# conectic_to_girouette.net
KiCad netlist of a schematic drawn in Altium Designer
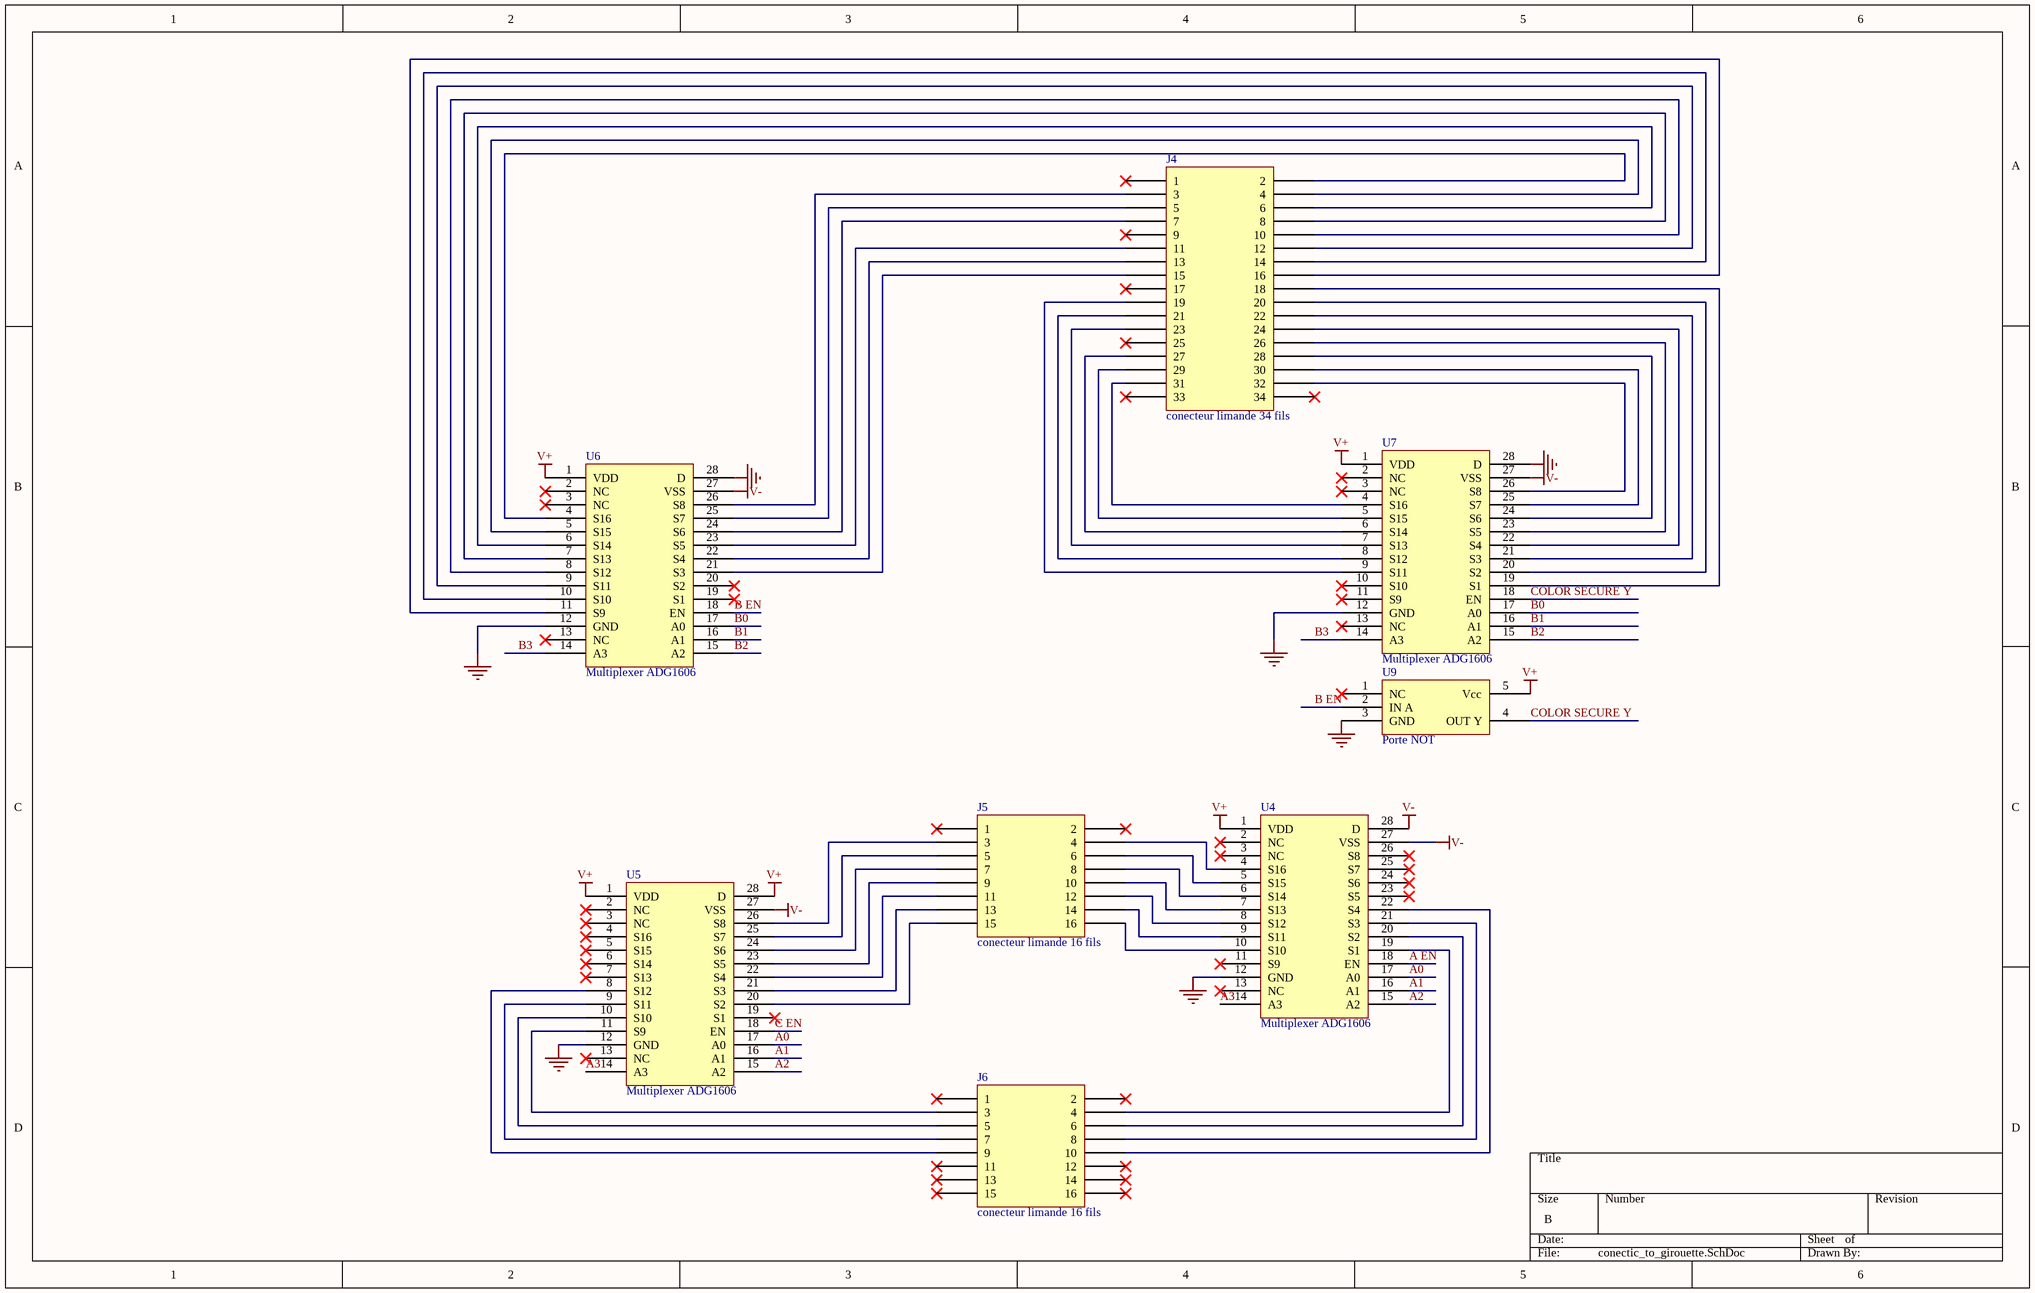
[diagram p0: conectic_to_girouette.SchDoc]

(export (version "E")
  (design (tool "Eeschema 10.0.6"))
  (components
    (comp (ref "J4")
      (value "conecteur limande 34 fils")
      (footprint "HTSS-117-01-T-DV-P-TR Connecteur 34 pins")
      (libsource (lib "lib_protoboard") (part "Limande 34 fils"))
    )
    (comp (ref "J5")
      (value "conecteur limande 16 fils")
      (footprint "M80-8541642 connecteur 16 pins")
      (libsource (lib "lib_protoboard") (part "Connecteur carte a carte"))
    )
    (comp (ref "J6")
      (value "conecteur limande 16 fils")
      (footprint "M80-8541642 connecteur 16 pins")
      (libsource (lib "lib_protoboard") (part "Connecteur carte a carte"))
    )
    (comp (ref "U4")
      (value "Multiplexer ADG1606")
      (footprint "TSOP65P640X120-28N")
      (libsource (lib "ADG1606") (part "Component_1"))
    )
    (comp (ref "U5")
      (value "Multiplexer ADG1606")
      (footprint "TSOP65P640X120-28N")
      (libsource (lib "ADG1606") (part "Component_1"))
    )
    (comp (ref "U6")
      (value "Multiplexer ADG1606")
      (footprint "TSOP65P640X120-28N")
      (libsource (lib "lib_protoboard") (part "ADG1606"))
    )
    (comp (ref "U7")
      (value "Multiplexer ADG1606")
      (footprint "TSOP65P640X120-28N")
      (libsource (lib "lib_protoboard") (part "ADG1606"))
    )
    (comp (ref "U9")
      (value "Porte NOT")
      (footprint "SOT65P210X110-5N")
      (libsource (lib "lib_protoboard") (part "Porte NOT"))
    )
  )
  (nets
    (net (code "1") (name "/A EN") (class "Default")
      (node (ref "U4") (pin "18") (pinfunction "EN_18") (pintype "passive"))
    )
    (net (code "2") (name "/A0") (class "Default")
      (node (ref "U4") (pin "17") (pinfunction "A0_17") (pintype "passive"))
      (node (ref "U5") (pin "17") (pinfunction "A0_17") (pintype "passive"))
    )
    (net (code "3") (name "/A1") (class "Default")
      (node (ref "U4") (pin "16") (pinfunction "A1_16") (pintype "passive"))
      (node (ref "U5") (pin "16") (pinfunction "A1_16") (pintype "passive"))
    )
    (net (code "4") (name "/A2") (class "Default")
      (node (ref "U4") (pin "15") (pinfunction "A2_15") (pintype "passive"))
      (node (ref "U5") (pin "15") (pinfunction "A2_15") (pintype "passive"))
    )
    (net (code "5") (name "/A3") (class "Default")
      (node (ref "U4") (pin "14") (pinfunction "A3_14") (pintype "passive"))
      (node (ref "U5") (pin "14") (pinfunction "A3_14") (pintype "passive"))
    )
    (net (code "6") (name "/B EN") (class "Default")
      (node (ref "U6") (pin "18") (pinfunction "EN_18") (pintype "passive"))
      (node (ref "U9") (pin "2") (pinfunction "IN_A_2") (pintype "passive"))
    )
    (net (code "7") (name "/B0") (class "Default")
      (node (ref "U6") (pin "17") (pinfunction "A0_17") (pintype "passive"))
      (node (ref "U7") (pin "17") (pinfunction "A0_17") (pintype "passive"))
    )
    (net (code "8") (name "/B1") (class "Default")
      (node (ref "U6") (pin "16") (pinfunction "A1_16") (pintype "passive"))
      (node (ref "U7") (pin "16") (pinfunction "A1_16") (pintype "passive"))
    )
    (net (code "9") (name "/B2") (class "Default")
      (node (ref "U6") (pin "15") (pinfunction "A2_15") (pintype "passive"))
      (node (ref "U7") (pin "15") (pinfunction "A2_15") (pintype "passive"))
    )
    (net (code "10") (name "/B3") (class "Default")
      (node (ref "U6") (pin "14") (pinfunction "A3_14") (pintype "passive"))
      (node (ref "U7") (pin "14") (pinfunction "A3_14") (pintype "passive"))
    )
    (net (code "11") (name "/C EN") (class "Default")
      (node (ref "U5") (pin "18") (pinfunction "EN_18") (pintype "passive"))
    )
    (net (code "12") (name "/COLOR SECURE Y") (class "Default")
      (node (ref "U7") (pin "18") (pinfunction "EN_18") (pintype "passive"))
      (node (ref "U9") (pin "4") (pinfunction "OUT_Y_4") (pintype "passive"))
    )
    (net (code "13") (name "GND") (class "Default")
      (node (ref "U4") (pin "12") (pinfunction "GND_12") (pintype "passive"))
      (node (ref "U5") (pin "12") (pinfunction "GND_12") (pintype "passive"))
      (node (ref "U6") (pin "12") (pinfunction "GND_12") (pintype "passive"))
      (node (ref "U6") (pin "28") (pinfunction "D_28") (pintype "passive"))
      (node (ref "U7") (pin "12") (pinfunction "GND_12") (pintype "passive"))
      (node (ref "U7") (pin "28") (pinfunction "D_28") (pintype "passive"))
      (node (ref "U9") (pin "3") (pinfunction "GND_3") (pintype "passive"))
    )
    (net (code "14") (name "Net-(U4-S1)") (class "Default")
      (node (ref "J6") (pin "4") (pinfunction "4_4") (pintype "passive"))
      (node (ref "U4") (pin "19") (pinfunction "S1_19") (pintype "passive"))
    )
    (net (code "15") (name "Net-(U4-S2)") (class "Default")
      (node (ref "J6") (pin "6") (pinfunction "6_6") (pintype "passive"))
      (node (ref "U4") (pin "20") (pinfunction "S2_20") (pintype "passive"))
    )
    (net (code "16") (name "Net-(U4-S3)") (class "Default")
      (node (ref "J6") (pin "8") (pinfunction "8_8") (pintype "passive"))
      (node (ref "U4") (pin "21") (pinfunction "S3_21") (pintype "passive"))
    )
    (net (code "17") (name "Net-(U4-S4)") (class "Default")
      (node (ref "J6") (pin "10") (pinfunction "10_10") (pintype "passive"))
      (node (ref "U4") (pin "22") (pinfunction "S4_22") (pintype "passive"))
    )
    (net (code "18") (name "Net-(U4-S10)") (class "Default")
      (node (ref "J5") (pin "16") (pinfunction "16_16") (pintype "passive"))
      (node (ref "U4") (pin "10") (pinfunction "S10_10") (pintype "passive"))
    )
    (net (code "19") (name "Net-(U4-S11)") (class "Default")
      (node (ref "J5") (pin "14") (pinfunction "14_14") (pintype "passive"))
      (node (ref "U4") (pin "9") (pinfunction "S11_9") (pintype "passive"))
    )
    (net (code "20") (name "Net-(U4-S12)") (class "Default")
      (node (ref "J5") (pin "12") (pinfunction "12_12") (pintype "passive"))
      (node (ref "U4") (pin "8") (pinfunction "S12_8") (pintype "passive"))
    )
    (net (code "21") (name "Net-(U4-S13)") (class "Default")
      (node (ref "J5") (pin "10") (pinfunction "10_10") (pintype "passive"))
      (node (ref "U4") (pin "7") (pinfunction "S13_7") (pintype "passive"))
    )
    (net (code "22") (name "Net-(U4-S14)") (class "Default")
      (node (ref "J5") (pin "8") (pinfunction "8_8") (pintype "passive"))
      (node (ref "U4") (pin "6") (pinfunction "S14_6") (pintype "passive"))
    )
    (net (code "23") (name "Net-(U4-S15)") (class "Default")
      (node (ref "J5") (pin "6") (pinfunction "6_6") (pintype "passive"))
      (node (ref "U4") (pin "5") (pinfunction "S15_5") (pintype "passive"))
    )
    (net (code "24") (name "Net-(U4-S16)") (class "Default")
      (node (ref "J5") (pin "4") (pinfunction "4_4") (pintype "passive"))
      (node (ref "U4") (pin "4") (pinfunction "S16_4") (pintype "passive"))
    )
    (net (code "25") (name "Net-(U5-S2)") (class "Default")
      (node (ref "J5") (pin "15") (pinfunction "15_15") (pintype "passive"))
      (node (ref "U5") (pin "20") (pinfunction "S2_20") (pintype "passive"))
    )
    (net (code "26") (name "Net-(U5-S3)") (class "Default")
      (node (ref "J5") (pin "13") (pinfunction "13_13") (pintype "passive"))
      (node (ref "U5") (pin "21") (pinfunction "S3_21") (pintype "passive"))
    )
    (net (code "27") (name "Net-(U5-S4)") (class "Default")
      (node (ref "J5") (pin "11") (pinfunction "11_11") (pintype "passive"))
      (node (ref "U5") (pin "22") (pinfunction "S4_22") (pintype "passive"))
    )
    (net (code "28") (name "Net-(U5-S5)") (class "Default")
      (node (ref "J5") (pin "9") (pinfunction "9_9") (pintype "passive"))
      (node (ref "U5") (pin "23") (pinfunction "S5_23") (pintype "passive"))
    )
    (net (code "29") (name "Net-(U5-S6)") (class "Default")
      (node (ref "J5") (pin "7") (pinfunction "7_7") (pintype "passive"))
      (node (ref "U5") (pin "24") (pinfunction "S6_24") (pintype "passive"))
    )
    (net (code "30") (name "Net-(U5-S7)") (class "Default")
      (node (ref "J5") (pin "5") (pinfunction "5_5") (pintype "passive"))
      (node (ref "U5") (pin "25") (pinfunction "S7_25") (pintype "passive"))
    )
    (net (code "31") (name "Net-(U5-S8)") (class "Default")
      (node (ref "J5") (pin "3") (pinfunction "3_3") (pintype "passive"))
      (node (ref "U5") (pin "26") (pinfunction "S8_26") (pintype "passive"))
    )
    (net (code "32") (name "Net-(U5-S9)") (class "Default")
      (node (ref "J6") (pin "3") (pinfunction "3_3") (pintype "passive"))
      (node (ref "U5") (pin "11") (pinfunction "S9_11") (pintype "passive"))
    )
    (net (code "33") (name "Net-(U5-S10)") (class "Default")
      (node (ref "J6") (pin "5") (pinfunction "5_5") (pintype "passive"))
      (node (ref "U5") (pin "10") (pinfunction "S10_10") (pintype "passive"))
    )
    (net (code "34") (name "Net-(U5-S11)") (class "Default")
      (node (ref "J6") (pin "7") (pinfunction "7_7") (pintype "passive"))
      (node (ref "U5") (pin "9") (pinfunction "S11_9") (pintype "passive"))
    )
    (net (code "35") (name "Net-(U5-S12)") (class "Default")
      (node (ref "J6") (pin "9") (pinfunction "9_9") (pintype "passive"))
      (node (ref "U5") (pin "8") (pinfunction "S12_8") (pintype "passive"))
    )
    (net (code "36") (name "Net-(U6-S3)") (class "Default")
      (node (ref "J4") (pin "15") (pinfunction "15_15") (pintype "passive"))
      (node (ref "U6") (pin "21") (pinfunction "S3_21") (pintype "passive"))
    )
    (net (code "37") (name "Net-(U6-S4)") (class "Default")
      (node (ref "J4") (pin "13") (pinfunction "13_13") (pintype "passive"))
      (node (ref "U6") (pin "22") (pinfunction "S4_22") (pintype "passive"))
    )
    (net (code "38") (name "Net-(U6-S5)") (class "Default")
      (node (ref "J4") (pin "11") (pinfunction "11_11") (pintype "passive"))
      (node (ref "U6") (pin "23") (pinfunction "S5_23") (pintype "passive"))
    )
    (net (code "39") (name "Net-(U6-S6)") (class "Default")
      (node (ref "J4") (pin "7") (pinfunction "7_7") (pintype "passive"))
      (node (ref "U6") (pin "24") (pinfunction "S6_24") (pintype "passive"))
    )
    (net (code "40") (name "Net-(U6-S7)") (class "Default")
      (node (ref "J4") (pin "5") (pinfunction "5_5") (pintype "passive"))
      (node (ref "U6") (pin "25") (pinfunction "S7_25") (pintype "passive"))
    )
    (net (code "41") (name "Net-(U6-S8)") (class "Default")
      (node (ref "J4") (pin "3") (pinfunction "3_3") (pintype "passive"))
      (node (ref "U6") (pin "26") (pinfunction "S8_26") (pintype "passive"))
    )
    (net (code "42") (name "Net-(U6-S9)") (class "Default")
      (node (ref "J4") (pin "16") (pinfunction "16_16") (pintype "passive"))
      (node (ref "U6") (pin "11") (pinfunction "S9_11") (pintype "passive"))
    )
    (net (code "43") (name "Net-(U6-S10)") (class "Default")
      (node (ref "J4") (pin "14") (pinfunction "14_14") (pintype "passive"))
      (node (ref "U6") (pin "10") (pinfunction "S10_10") (pintype "passive"))
    )
    (net (code "44") (name "Net-(U6-S11)") (class "Default")
      (node (ref "J4") (pin "12") (pinfunction "12_12") (pintype "passive"))
      (node (ref "U6") (pin "9") (pinfunction "S11_9") (pintype "passive"))
    )
    (net (code "45") (name "Net-(U6-S12)") (class "Default")
      (node (ref "J4") (pin "10") (pinfunction "10_10") (pintype "passive"))
      (node (ref "U6") (pin "8") (pinfunction "S12_8") (pintype "passive"))
    )
    (net (code "46") (name "Net-(U6-S13)") (class "Default")
      (node (ref "J4") (pin "8") (pinfunction "8_8") (pintype "passive"))
      (node (ref "U6") (pin "7") (pinfunction "S13_7") (pintype "passive"))
    )
    (net (code "47") (name "Net-(U6-S14)") (class "Default")
      (node (ref "J4") (pin "6") (pinfunction "6_6") (pintype "passive"))
      (node (ref "U6") (pin "6") (pinfunction "S14_6") (pintype "passive"))
    )
    (net (code "48") (name "Net-(U6-S15)") (class "Default")
      (node (ref "J4") (pin "4") (pinfunction "4_4") (pintype "passive"))
      (node (ref "U6") (pin "5") (pinfunction "S15_5") (pintype "passive"))
    )
    (net (code "49") (name "Net-(U6-S16)") (class "Default")
      (node (ref "J4") (pin "2") (pinfunction "2_2") (pintype "passive"))
      (node (ref "U6") (pin "4") (pinfunction "S16_4") (pintype "passive"))
    )
    (net (code "50") (name "Net-(U7-S1)") (class "Default")
      (node (ref "J4") (pin "18") (pinfunction "18_18") (pintype "passive"))
      (node (ref "U7") (pin "19") (pinfunction "S1_19") (pintype "passive"))
    )
    (net (code "51") (name "Net-(U7-S2)") (class "Default")
      (node (ref "J4") (pin "20") (pinfunction "20_20") (pintype "passive"))
      (node (ref "U7") (pin "20") (pinfunction "S2_20") (pintype "passive"))
    )
    (net (code "52") (name "Net-(U7-S3)") (class "Default")
      (node (ref "J4") (pin "22") (pinfunction "22_22") (pintype "passive"))
      (node (ref "U7") (pin "21") (pinfunction "S3_21") (pintype "passive"))
    )
    (net (code "53") (name "Net-(U7-S4)") (class "Default")
      (node (ref "J4") (pin "24") (pinfunction "24_24") (pintype "passive"))
      (node (ref "U7") (pin "22") (pinfunction "S4_22") (pintype "passive"))
    )
    (net (code "54") (name "Net-(U7-S5)") (class "Default")
      (node (ref "J4") (pin "26") (pinfunction "26_26") (pintype "passive"))
      (node (ref "U7") (pin "23") (pinfunction "S5_23") (pintype "passive"))
    )
    (net (code "55") (name "Net-(U7-S6)") (class "Default")
      (node (ref "J4") (pin "28") (pinfunction "28_28") (pintype "passive"))
      (node (ref "U7") (pin "24") (pinfunction "S6_24") (pintype "passive"))
    )
    (net (code "56") (name "Net-(U7-S7)") (class "Default")
      (node (ref "J4") (pin "30") (pinfunction "30_30") (pintype "passive"))
      (node (ref "U7") (pin "25") (pinfunction "S7_25") (pintype "passive"))
    )
    (net (code "57") (name "Net-(U7-S8)") (class "Default")
      (node (ref "J4") (pin "32") (pinfunction "32_32") (pintype "passive"))
      (node (ref "U7") (pin "26") (pinfunction "S8_26") (pintype "passive"))
    )
    (net (code "58") (name "Net-(U7-S11)") (class "Default")
      (node (ref "J4") (pin "19") (pinfunction "19_19") (pintype "passive"))
      (node (ref "U7") (pin "9") (pinfunction "S11_9") (pintype "passive"))
    )
    (net (code "59") (name "Net-(U7-S12)") (class "Default")
      (node (ref "J4") (pin "21") (pinfunction "21_21") (pintype "passive"))
      (node (ref "U7") (pin "8") (pinfunction "S12_8") (pintype "passive"))
    )
    (net (code "60") (name "Net-(U7-S13)") (class "Default")
      (node (ref "J4") (pin "23") (pinfunction "23_23") (pintype "passive"))
      (node (ref "U7") (pin "7") (pinfunction "S13_7") (pintype "passive"))
    )
    (net (code "61") (name "Net-(U7-S14)") (class "Default")
      (node (ref "J4") (pin "27") (pinfunction "27_27") (pintype "passive"))
      (node (ref "U7") (pin "6") (pinfunction "S14_6") (pintype "passive"))
    )
    (net (code "62") (name "Net-(U7-S15)") (class "Default")
      (node (ref "J4") (pin "29") (pinfunction "29_29") (pintype "passive"))
      (node (ref "U7") (pin "5") (pinfunction "S15_5") (pintype "passive"))
    )
    (net (code "63") (name "Net-(U7-S16)") (class "Default")
      (node (ref "J4") (pin "31") (pinfunction "31_31") (pintype "passive"))
      (node (ref "U7") (pin "4") (pinfunction "S16_4") (pintype "passive"))
    )
    (net (code "64") (name "V+") (class "Default")
      (node (ref "U4") (pin "1") (pinfunction "VDD_1") (pintype "passive"))
      (node (ref "U5") (pin "1") (pinfunction "VDD_1") (pintype "passive"))
      (node (ref "U5") (pin "28") (pinfunction "D_28") (pintype "passive"))
      (node (ref "U6") (pin "1") (pinfunction "VDD_1") (pintype "passive"))
      (node (ref "U7") (pin "1") (pinfunction "VDD_1") (pintype "passive"))
      (node (ref "U9") (pin "5") (pinfunction "Vcc_5") (pintype "passive"))
    )
    (net (code "65") (name "V-") (class "Default")
      (node (ref "U4") (pin "27") (pinfunction "VSS_27") (pintype "passive"))
      (node (ref "U4") (pin "28") (pinfunction "D_28") (pintype "passive"))
      (node (ref "U5") (pin "27") (pinfunction "VSS_27") (pintype "passive"))
      (node (ref "U6") (pin "27") (pinfunction "VSS_27") (pintype "passive"))
      (node (ref "U7") (pin "27") (pinfunction "VSS_27") (pintype "passive"))
    )
    (net (code "66") (name "unconnected-(J4-Pad1)") (class "Default")
      (node (ref "J4") (pin "1") (pinfunction "1_1") (pintype "passive+no_connect"))
    )
    (net (code "67") (name "unconnected-(J4-Pad9)") (class "Default")
      (node (ref "J4") (pin "9") (pinfunction "9_9") (pintype "passive+no_connect"))
    )
    (net (code "68") (name "unconnected-(J4-Pad17)") (class "Default")
      (node (ref "J4") (pin "17") (pinfunction "17_17") (pintype "passive+no_connect"))
    )
    (net (code "69") (name "unconnected-(J4-Pad25)") (class "Default")
      (node (ref "J4") (pin "25") (pinfunction "25_25") (pintype "passive+no_connect"))
    )
    (net (code "70") (name "unconnected-(J4-Pad33)") (class "Default")
      (node (ref "J4") (pin "33") (pinfunction "33_33") (pintype "passive+no_connect"))
    )
    (net (code "71") (name "unconnected-(J4-Pad34)") (class "Default")
      (node (ref "J4") (pin "34") (pinfunction "34_34") (pintype "passive+no_connect"))
    )
    (net (code "72") (name "unconnected-(J5-Pad1)") (class "Default")
      (node (ref "J5") (pin "1") (pinfunction "1_1") (pintype "passive+no_connect"))
    )
    (net (code "73") (name "unconnected-(J5-Pad2)") (class "Default")
      (node (ref "J5") (pin "2") (pinfunction "2_2") (pintype "passive+no_connect"))
    )
    (net (code "74") (name "unconnected-(J6-Pad1)") (class "Default")
      (node (ref "J6") (pin "1") (pinfunction "1_1") (pintype "passive+no_connect"))
    )
    (net (code "75") (name "unconnected-(J6-Pad2)") (class "Default")
      (node (ref "J6") (pin "2") (pinfunction "2_2") (pintype "passive+no_connect"))
    )
    (net (code "76") (name "unconnected-(J6-Pad11)") (class "Default")
      (node (ref "J6") (pin "11") (pinfunction "11_11") (pintype "passive+no_connect"))
    )
    (net (code "77") (name "unconnected-(J6-Pad12)") (class "Default")
      (node (ref "J6") (pin "12") (pinfunction "12_12") (pintype "passive+no_connect"))
    )
    (net (code "78") (name "unconnected-(J6-Pad13)") (class "Default")
      (node (ref "J6") (pin "13") (pinfunction "13_13") (pintype "passive+no_connect"))
    )
    (net (code "79") (name "unconnected-(J6-Pad14)") (class "Default")
      (node (ref "J6") (pin "14") (pinfunction "14_14") (pintype "passive+no_connect"))
    )
    (net (code "80") (name "unconnected-(J6-Pad15)") (class "Default")
      (node (ref "J6") (pin "15") (pinfunction "15_15") (pintype "passive+no_connect"))
    )
    (net (code "81") (name "unconnected-(J6-Pad16)") (class "Default")
      (node (ref "J6") (pin "16") (pinfunction "16_16") (pintype "passive+no_connect"))
    )
    (net (code "82") (name "unconnected-(U4-NC-Pad2)") (class "Default")
      (node (ref "U4") (pin "2") (pinfunction "NC_2") (pintype "passive+no_connect"))
    )
    (net (code "83") (name "unconnected-(U4-NC-Pad3)") (class "Default")
      (node (ref "U4") (pin "3") (pinfunction "NC_3") (pintype "passive+no_connect"))
    )
    (net (code "84") (name "unconnected-(U4-NC-Pad13)") (class "Default")
      (node (ref "U4") (pin "13") (pinfunction "NC_13") (pintype "passive+no_connect"))
    )
    (net (code "85") (name "unconnected-(U4-S5-Pad23)") (class "Default")
      (node (ref "U4") (pin "23") (pinfunction "S5_23") (pintype "passive+no_connect"))
    )
    (net (code "86") (name "unconnected-(U4-S6-Pad24)") (class "Default")
      (node (ref "U4") (pin "24") (pinfunction "S6_24") (pintype "passive+no_connect"))
    )
    (net (code "87") (name "unconnected-(U4-S7-Pad25)") (class "Default")
      (node (ref "U4") (pin "25") (pinfunction "S7_25") (pintype "passive+no_connect"))
    )
    (net (code "88") (name "unconnected-(U4-S8-Pad26)") (class "Default")
      (node (ref "U4") (pin "26") (pinfunction "S8_26") (pintype "passive+no_connect"))
    )
    (net (code "89") (name "unconnected-(U4-S9-Pad11)") (class "Default")
      (node (ref "U4") (pin "11") (pinfunction "S9_11") (pintype "passive+no_connect"))
    )
    (net (code "90") (name "unconnected-(U5-NC-Pad2)") (class "Default")
      (node (ref "U5") (pin "2") (pinfunction "NC_2") (pintype "passive+no_connect"))
    )
    (net (code "91") (name "unconnected-(U5-NC-Pad3)") (class "Default")
      (node (ref "U5") (pin "3") (pinfunction "NC_3") (pintype "passive+no_connect"))
    )
    (net (code "92") (name "unconnected-(U5-NC-Pad13)") (class "Default")
      (node (ref "U5") (pin "13") (pinfunction "NC_13") (pintype "passive+no_connect"))
    )
    (net (code "93") (name "unconnected-(U5-S1-Pad19)") (class "Default")
      (node (ref "U5") (pin "19") (pinfunction "S1_19") (pintype "passive+no_connect"))
    )
    (net (code "94") (name "unconnected-(U5-S13-Pad7)") (class "Default")
      (node (ref "U5") (pin "7") (pinfunction "S13_7") (pintype "passive+no_connect"))
    )
    (net (code "95") (name "unconnected-(U5-S14-Pad6)") (class "Default")
      (node (ref "U5") (pin "6") (pinfunction "S14_6") (pintype "passive+no_connect"))
    )
    (net (code "96") (name "unconnected-(U5-S15-Pad5)") (class "Default")
      (node (ref "U5") (pin "5") (pinfunction "S15_5") (pintype "passive+no_connect"))
    )
    (net (code "97") (name "unconnected-(U5-S16-Pad4)") (class "Default")
      (node (ref "U5") (pin "4") (pinfunction "S16_4") (pintype "passive+no_connect"))
    )
    (net (code "98") (name "unconnected-(U6-NC-Pad2)") (class "Default")
      (node (ref "U6") (pin "2") (pinfunction "NC_2") (pintype "passive+no_connect"))
    )
    (net (code "99") (name "unconnected-(U6-NC-Pad3)") (class "Default")
      (node (ref "U6") (pin "3") (pinfunction "NC_3") (pintype "passive+no_connect"))
    )
    (net (code "100") (name "unconnected-(U6-NC-Pad13)") (class "Default")
      (node (ref "U6") (pin "13") (pinfunction "NC_13") (pintype "passive+no_connect"))
    )
    (net (code "101") (name "unconnected-(U6-S1-Pad19)") (class "Default")
      (node (ref "U6") (pin "19") (pinfunction "S1_19") (pintype "passive+no_connect"))
    )
    (net (code "102") (name "unconnected-(U6-S2-Pad20)") (class "Default")
      (node (ref "U6") (pin "20") (pinfunction "S2_20") (pintype "passive+no_connect"))
    )
    (net (code "103") (name "unconnected-(U7-NC-Pad2)") (class "Default")
      (node (ref "U7") (pin "2") (pinfunction "NC_2") (pintype "passive+no_connect"))
    )
    (net (code "104") (name "unconnected-(U7-NC-Pad3)") (class "Default")
      (node (ref "U7") (pin "3") (pinfunction "NC_3") (pintype "passive+no_connect"))
    )
    (net (code "105") (name "unconnected-(U7-NC-Pad13)") (class "Default")
      (node (ref "U7") (pin "13") (pinfunction "NC_13") (pintype "passive+no_connect"))
    )
    (net (code "106") (name "unconnected-(U7-S9-Pad11)") (class "Default")
      (node (ref "U7") (pin "11") (pinfunction "S9_11") (pintype "passive+no_connect"))
    )
    (net (code "107") (name "unconnected-(U7-S10-Pad10)") (class "Default")
      (node (ref "U7") (pin "10") (pinfunction "S10_10") (pintype "passive+no_connect"))
    )
    (net (code "108") (name "unconnected-(U9-NC-Pad1)") (class "Default")
      (node (ref "U9") (pin "1") (pinfunction "NC_1") (pintype "passive+no_connect"))
    )
  )
)
